# Adafruit_IS31FL3731_Breakout.net
KiCad netlist of a schematic drawn in EAGLE
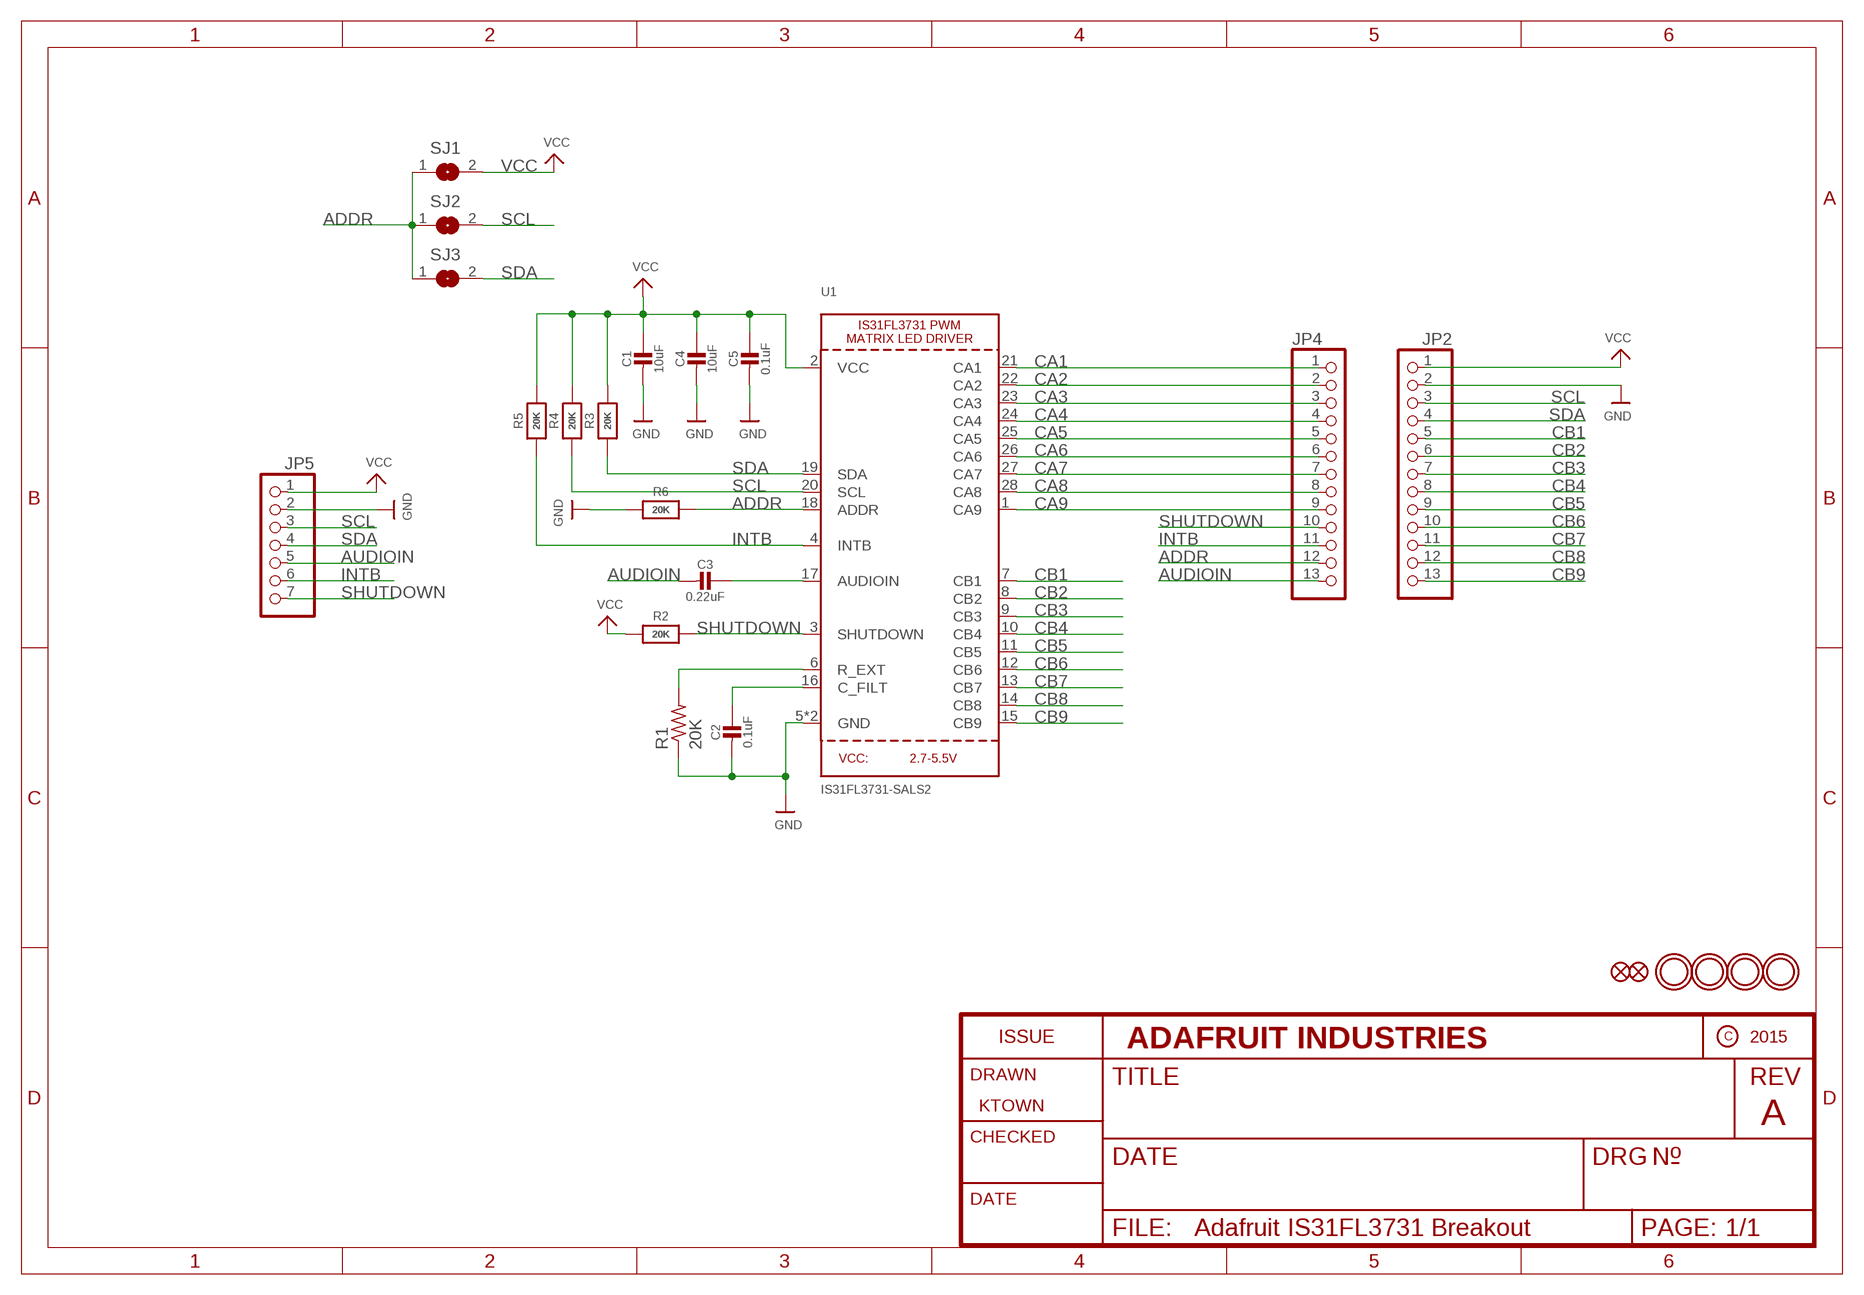
[diagram p0: schematic, sheet 1]

(export (version "E")
  (design (tool "Eeschema 10.0.6"))
  (components
    (comp (ref "C1")
      (value "10uF")
      (footprint "eagle-import:0805-NO")
      (libsource (lib "eagle-import") (part "CAP_CERAMIC0805-NOOUTLINE"))
    )
    (comp (ref "C2")
      (value "0.1uF")
      (footprint "eagle-import:0805-NO")
      (libsource (lib "eagle-import") (part "CAP_CERAMIC0805-NOOUTLINE"))
    )
    (comp (ref "C3")
      (value "0.22uF")
      (footprint "eagle-import:0805-NO")
      (libsource (lib "eagle-import") (part "CAP_CERAMIC0805-NOOUTLINE"))
    )
    (comp (ref "C4")
      (value "10uF")
      (footprint "eagle-import:0805-NO")
      (libsource (lib "eagle-import") (part "CAP_CERAMIC0805-NOOUTLINE"))
    )
    (comp (ref "C5")
      (value "0.1uF")
      (footprint "eagle-import:0805-NO")
      (libsource (lib "eagle-import") (part "CAP_CERAMIC0805-NOOUTLINE"))
    )
    (comp (ref "FID1")
      (value "FIDUCIAL\"\"")
      (footprint "eagle-import:FIDUCIAL_1MM")
      (libsource (lib "eagle-import") (part "FIDUCIAL{dblquote}{dblquote}"))
    )
    (comp (ref "FID2")
      (value "FIDUCIAL\"\"")
      (footprint "eagle-import:FIDUCIAL_1MM")
      (libsource (lib "eagle-import") (part "FIDUCIAL{dblquote}{dblquote}"))
    )
    (comp (ref "JP2")
      (value "HEADER-1X13")
      (footprint "eagle-import:1X13_ROUND_70")
      (libsource (lib "eagle-import") (part "HEADER-1X13"))
    )
    (comp (ref "JP4")
      (value "HEADER-1X13")
      (footprint "eagle-import:1X13_ROUND_70")
      (libsource (lib "eagle-import") (part "HEADER-1X13"))
    )
    (comp (ref "JP5")
      (value "HEADER-1X7THICKER")
      (footprint "eagle-import:1X07_ROUND_76")
      (libsource (lib "eagle-import") (part "HEADER-1X7THICKER"))
    )
    (comp (ref "R1")
      (value "20K")
      (footprint "eagle-import:0805-THM")
      (libsource (lib "eagle-import") (part "FLIPFLOP-RES"))
    )
    (comp (ref "R2")
      (value "20K")
      (footprint "eagle-import:0805-NO")
      (libsource (lib "eagle-import") (part "RESISTOR0805_NOOUTLINE"))
    )
    (comp (ref "R3")
      (value "20K")
      (footprint "eagle-import:0805-NO")
      (libsource (lib "eagle-import") (part "RESISTOR0805_NOOUTLINE"))
    )
    (comp (ref "R4")
      (value "20K")
      (footprint "eagle-import:0805-NO")
      (libsource (lib "eagle-import") (part "RESISTOR0805_NOOUTLINE"))
    )
    (comp (ref "R5")
      (value "20K")
      (footprint "eagle-import:0805-NO")
      (libsource (lib "eagle-import") (part "RESISTOR0805_NOOUTLINE"))
    )
    (comp (ref "R6")
      (value "20K")
      (footprint "eagle-import:0805-NO")
      (libsource (lib "eagle-import") (part "RESISTOR0805_NOOUTLINE"))
    )
    (comp (ref "SJ1")
      (value "SOLDERJUMPER")
      (footprint "eagle-import:SOLDERJUMPER_ARROW_NOPASTE")
      (libsource (lib "eagle-import") (part "SOLDERJUMPER"))
    )
    (comp (ref "SJ2")
      (value "SOLDERJUMPER")
      (footprint "eagle-import:SOLDERJUMPER_ARROW_NOPASTE")
      (libsource (lib "eagle-import") (part "SOLDERJUMPER"))
    )
    (comp (ref "SJ3")
      (value "SOLDERJUMPER")
      (footprint "eagle-import:SOLDERJUMPER_ARROW_NOPASTE")
      (libsource (lib "eagle-import") (part "SOLDERJUMPER"))
    )
    (comp (ref "U$3")
      (value "MOUNTINGHOLE2.5")
      (footprint "eagle-import:MOUNTINGHOLE_2.5_PLATED")
      (libsource (lib "eagle-import") (part "MOUNTINGHOLE2.5"))
    )
    (comp (ref "U$4")
      (value "MOUNTINGHOLE2.5")
      (footprint "eagle-import:MOUNTINGHOLE_2.5_PLATED")
      (libsource (lib "eagle-import") (part "MOUNTINGHOLE2.5"))
    )
    (comp (ref "U$5")
      (value "MOUNTINGHOLE2.5")
      (footprint "eagle-import:MOUNTINGHOLE_2.5_PLATED")
      (libsource (lib "eagle-import") (part "MOUNTINGHOLE2.5"))
    )
    (comp (ref "U$6")
      (value "MOUNTINGHOLE2.5")
      (footprint "eagle-import:MOUNTINGHOLE_2.5_PLATED")
      (libsource (lib "eagle-import") (part "MOUNTINGHOLE2.5"))
    )
    (comp (ref "U1")
      (value "IS31FL3731-SALS2")
      (footprint "eagle-import:QFN28_4MM_0.4MM")
      (libsource (lib "eagle-import") (part "IS31FL3731QFN"))
    )
  )
  (nets
    (net (code "1") (name "/ADDR") (class "Default")
      (node (ref "JP4") (pin "12") (pinfunction "12_12") (pintype "passive"))
      (node (ref "R6") (pin "2") (pinfunction "2_2") (pintype "passive"))
      (node (ref "SJ1") (pin "1") (pinfunction "1_1") (pintype "passive"))
      (node (ref "SJ2") (pin "1") (pinfunction "1_1") (pintype "passive"))
      (node (ref "SJ3") (pin "1") (pinfunction "1_1") (pintype "passive"))
      (node (ref "U1") (pin "18") (pinfunction "ADDR_18") (pintype "bidirectional"))
    )
    (net (code "2") (name "/AUDIOIN") (class "Default")
      (node (ref "C3") (pin "2") (pinfunction "2_2") (pintype "passive"))
      (node (ref "JP4") (pin "13") (pinfunction "13_13") (pintype "passive"))
      (node (ref "JP5") (pin "5") (pinfunction "5_5") (pintype "passive"))
    )
    (net (code "3") (name "/CA1") (class "Default")
      (node (ref "JP4") (pin "1") (pinfunction "1_1") (pintype "passive"))
      (node (ref "U1") (pin "21") (pinfunction "CA1_21") (pintype "bidirectional"))
    )
    (net (code "4") (name "/CA2") (class "Default")
      (node (ref "JP4") (pin "2") (pinfunction "2_2") (pintype "passive"))
      (node (ref "U1") (pin "22") (pinfunction "CA2_22") (pintype "bidirectional"))
    )
    (net (code "5") (name "/CA3") (class "Default")
      (node (ref "JP4") (pin "3") (pinfunction "3_3") (pintype "passive"))
      (node (ref "U1") (pin "23") (pinfunction "CA3_23") (pintype "bidirectional"))
    )
    (net (code "6") (name "/CA4") (class "Default")
      (node (ref "JP4") (pin "4") (pinfunction "4_4") (pintype "passive"))
      (node (ref "U1") (pin "24") (pinfunction "CA4_24") (pintype "bidirectional"))
    )
    (net (code "7") (name "/CA5") (class "Default")
      (node (ref "JP4") (pin "5") (pinfunction "5_5") (pintype "passive"))
      (node (ref "U1") (pin "25") (pinfunction "CA5_25") (pintype "bidirectional"))
    )
    (net (code "8") (name "/CA6") (class "Default")
      (node (ref "JP4") (pin "6") (pinfunction "6_6") (pintype "passive"))
      (node (ref "U1") (pin "26") (pinfunction "CA6_26") (pintype "bidirectional"))
    )
    (net (code "9") (name "/CA7") (class "Default")
      (node (ref "JP4") (pin "7") (pinfunction "7_7") (pintype "passive"))
      (node (ref "U1") (pin "27") (pinfunction "CA7_27") (pintype "bidirectional"))
    )
    (net (code "10") (name "/CA8") (class "Default")
      (node (ref "JP4") (pin "8") (pinfunction "8_8") (pintype "passive"))
      (node (ref "U1") (pin "28") (pinfunction "CA8_28") (pintype "bidirectional"))
    )
    (net (code "11") (name "/CA9") (class "Default")
      (node (ref "JP4") (pin "9") (pinfunction "9_9") (pintype "passive"))
      (node (ref "U1") (pin "1") (pinfunction "CA9_1") (pintype "bidirectional"))
    )
    (net (code "12") (name "/CB1") (class "Default")
      (node (ref "JP2") (pin "5") (pinfunction "5_5") (pintype "passive"))
      (node (ref "U1") (pin "7") (pinfunction "CB1_7") (pintype "bidirectional"))
    )
    (net (code "13") (name "/CB2") (class "Default")
      (node (ref "JP2") (pin "6") (pinfunction "6_6") (pintype "passive"))
      (node (ref "U1") (pin "8") (pinfunction "CB2_8") (pintype "bidirectional"))
    )
    (net (code "14") (name "/CB3") (class "Default")
      (node (ref "JP2") (pin "7") (pinfunction "7_7") (pintype "passive"))
      (node (ref "U1") (pin "9") (pinfunction "CB3_9") (pintype "bidirectional"))
    )
    (net (code "15") (name "/CB4") (class "Default")
      (node (ref "JP2") (pin "8") (pinfunction "8_8") (pintype "passive"))
      (node (ref "U1") (pin "10") (pinfunction "CB4_10") (pintype "bidirectional"))
    )
    (net (code "16") (name "/CB5") (class "Default")
      (node (ref "JP2") (pin "9") (pinfunction "9_9") (pintype "passive"))
      (node (ref "U1") (pin "11") (pinfunction "CB5_11") (pintype "bidirectional"))
    )
    (net (code "17") (name "/CB6") (class "Default")
      (node (ref "JP2") (pin "10") (pinfunction "10_10") (pintype "passive"))
      (node (ref "U1") (pin "12") (pinfunction "CB6_12") (pintype "bidirectional"))
    )
    (net (code "18") (name "/CB7") (class "Default")
      (node (ref "JP2") (pin "11") (pinfunction "11_11") (pintype "passive"))
      (node (ref "U1") (pin "13") (pinfunction "CB7_13") (pintype "bidirectional"))
    )
    (net (code "19") (name "/CB8") (class "Default")
      (node (ref "JP2") (pin "12") (pinfunction "12_12") (pintype "passive"))
      (node (ref "U1") (pin "14") (pinfunction "CB8_14") (pintype "bidirectional"))
    )
    (net (code "20") (name "/CB9") (class "Default")
      (node (ref "JP2") (pin "13") (pinfunction "13_13") (pintype "passive"))
      (node (ref "U1") (pin "15") (pinfunction "CB9_15") (pintype "bidirectional"))
    )
    (net (code "21") (name "/INTB") (class "Default")
      (node (ref "JP4") (pin "11") (pinfunction "11_11") (pintype "passive"))
      (node (ref "JP5") (pin "6") (pinfunction "6_6") (pintype "passive"))
      (node (ref "R5") (pin "1") (pinfunction "1_1") (pintype "passive"))
      (node (ref "U1") (pin "4") (pinfunction "INTB_4") (pintype "output"))
    )
    (net (code "22") (name "/SCL") (class "Default")
      (node (ref "JP2") (pin "3") (pinfunction "3_3") (pintype "passive"))
      (node (ref "JP5") (pin "3") (pinfunction "3_3") (pintype "passive"))
      (node (ref "R4") (pin "1") (pinfunction "1_1") (pintype "passive"))
      (node (ref "SJ2") (pin "2") (pinfunction "2_2") (pintype "passive"))
      (node (ref "U1") (pin "20") (pinfunction "SCL_20") (pintype "bidirectional"))
    )
    (net (code "23") (name "/SDA") (class "Default")
      (node (ref "JP2") (pin "4") (pinfunction "4_4") (pintype "passive"))
      (node (ref "JP5") (pin "4") (pinfunction "4_4") (pintype "passive"))
      (node (ref "R3") (pin "1") (pinfunction "1_1") (pintype "passive"))
      (node (ref "SJ3") (pin "2") (pinfunction "2_2") (pintype "passive"))
      (node (ref "U1") (pin "19") (pinfunction "SDA_19") (pintype "bidirectional"))
    )
    (net (code "24") (name "/SHUTDOWN") (class "Default")
      (node (ref "JP4") (pin "10") (pinfunction "10_10") (pintype "passive"))
      (node (ref "JP5") (pin "7") (pinfunction "7_7") (pintype "passive"))
      (node (ref "R2") (pin "2") (pinfunction "2_2") (pintype "passive"))
      (node (ref "U1") (pin "3") (pinfunction "SHUTDOWN_3") (pintype "input"))
    )
    (net (code "25") (name "GND") (class "Default")
      (node (ref "C1") (pin "2") (pinfunction "2_2") (pintype "passive"))
      (node (ref "C2") (pin "2") (pinfunction "2_2") (pintype "passive"))
      (node (ref "C4") (pin "2") (pinfunction "2_2") (pintype "passive"))
      (node (ref "C5") (pin "2") (pinfunction "2_2") (pintype "passive"))
      (node (ref "JP2") (pin "2") (pinfunction "2_2") (pintype "passive"))
      (node (ref "JP5") (pin "2") (pinfunction "2_2") (pintype "passive"))
      (node (ref "R1") (pin "1") (pinfunction "1_1") (pintype "passive"))
      (node (ref "R6") (pin "1") (pinfunction "1_1") (pintype "passive"))
      (node (ref "U1") (pin "5") (pinfunction "GND_5") (pintype "power_in"))
      (node (ref "U1") (pin "THERMAL") (pinfunction "GND_THERMAL") (pintype "power_in"))
    )
    (net (code "26") (name "Net-(U1-AUDIOIN)") (class "Default")
      (node (ref "C3") (pin "1") (pinfunction "1_1") (pintype "passive"))
      (node (ref "U1") (pin "17") (pinfunction "AUDIOIN_17") (pintype "input"))
    )
    (net (code "27") (name "Net-(U1-C_FILT)") (class "Default")
      (node (ref "C2") (pin "1") (pinfunction "1_1") (pintype "passive"))
      (node (ref "U1") (pin "16") (pinfunction "C_FILT_16") (pintype "bidirectional"))
    )
    (net (code "28") (name "Net-(U1-R_EXT)") (class "Default")
      (node (ref "R1") (pin "2") (pinfunction "2_2") (pintype "passive"))
      (node (ref "U1") (pin "6") (pinfunction "R_EXT_6") (pintype "bidirectional"))
    )
    (net (code "29") (name "VCC") (class "Default")
      (node (ref "C1") (pin "1") (pinfunction "1_1") (pintype "passive"))
      (node (ref "C4") (pin "1") (pinfunction "1_1") (pintype "passive"))
      (node (ref "C5") (pin "1") (pinfunction "1_1") (pintype "passive"))
      (node (ref "JP2") (pin "1") (pinfunction "1_1") (pintype "passive"))
      (node (ref "JP5") (pin "1") (pinfunction "1_1") (pintype "passive"))
      (node (ref "R2") (pin "1") (pinfunction "1_1") (pintype "passive"))
      (node (ref "R3") (pin "2") (pinfunction "2_2") (pintype "passive"))
      (node (ref "R4") (pin "2") (pinfunction "2_2") (pintype "passive"))
      (node (ref "R5") (pin "2") (pinfunction "2_2") (pintype "passive"))
      (node (ref "SJ1") (pin "2") (pinfunction "2_2") (pintype "passive"))
      (node (ref "U1") (pin "2") (pinfunction "VCC_2") (pintype "power_in"))
    )
  )
)
